# main_board.net
KiCad netlist of a schematic drawn in EAGLE
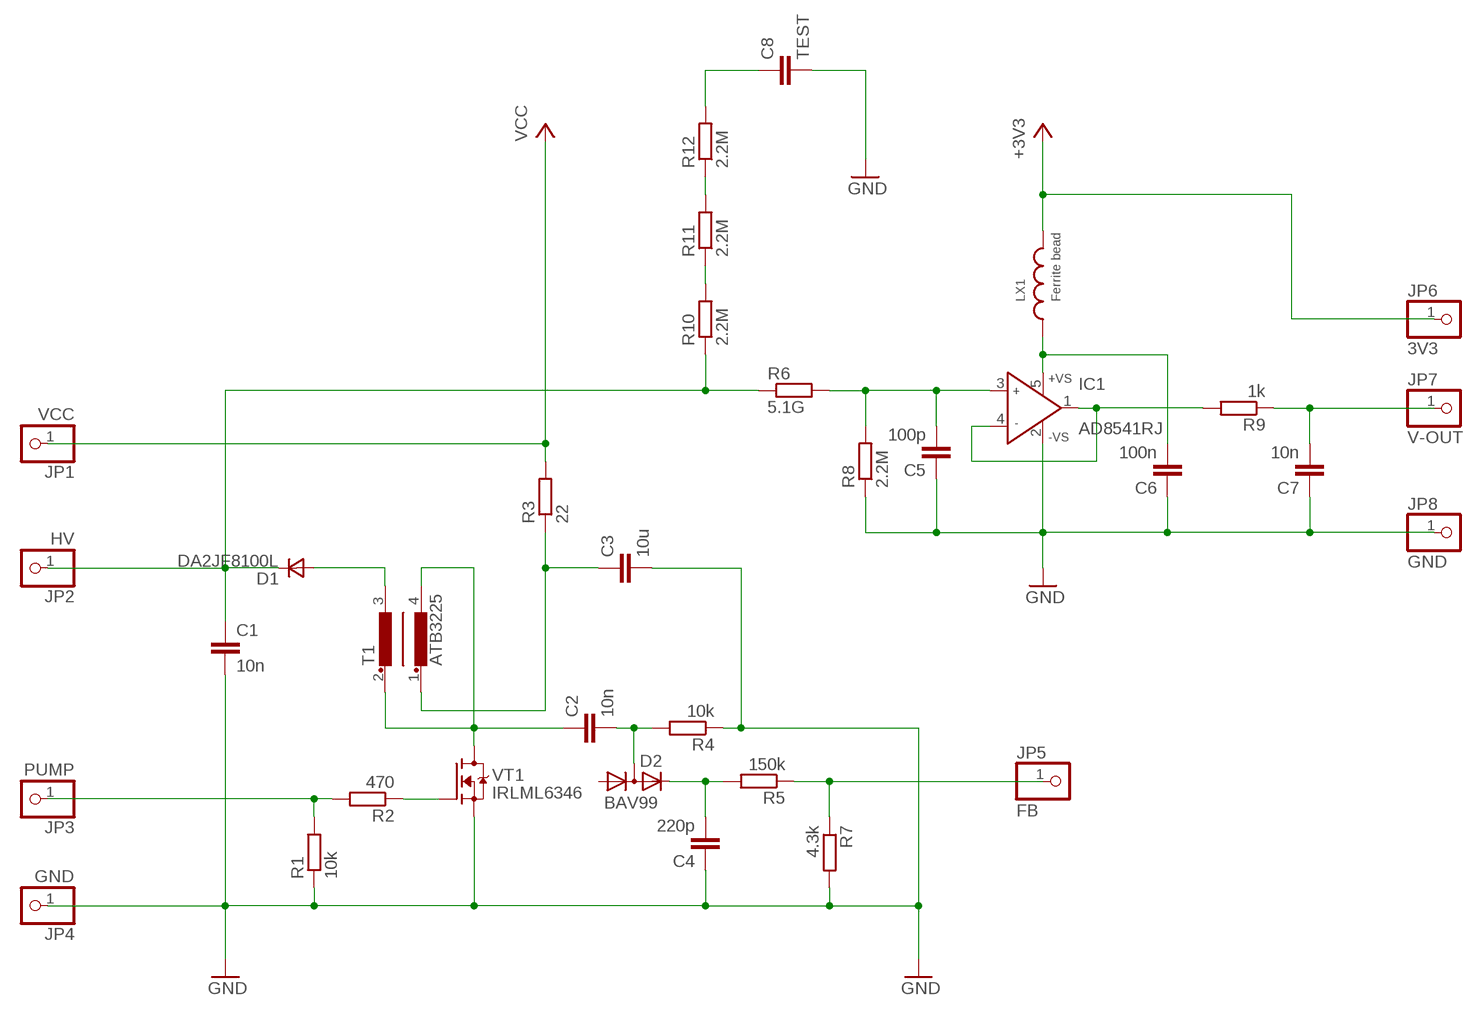
[diagram p0: schematic, sheet 1]

(export (version "E")
  (design (tool "Eeschema 10.0.6"))
  (components
    (comp (ref "C1")
      (value "10n")
      (footprint "eagle-import:C1206")
      (libsource (lib "eagle-import") (part "C-EUC1206"))
    )
    (comp (ref "C2")
      (value "10n")
      (footprint "eagle-import:C0805")
      (libsource (lib "eagle-import") (part "C-EUC0805"))
    )
    (comp (ref "C3")
      (value "10u")
      (footprint "eagle-import:C0805")
      (libsource (lib "eagle-import") (part "C-EUC0805"))
    )
    (comp (ref "C4")
      (value "220p")
      (footprint "eagle-import:C0805")
      (libsource (lib "eagle-import") (part "C-EUC0805"))
    )
    (comp (ref "C5")
      (value "100p")
      (footprint "eagle-import:C0805")
      (libsource (lib "eagle-import") (part "C-EUC0805"))
    )
    (comp (ref "C6")
      (value "100n")
      (footprint "eagle-import:C0805")
      (libsource (lib "eagle-import") (part "C-EUC0805"))
    )
    (comp (ref "C7")
      (value "10n")
      (footprint "eagle-import:C0805")
      (libsource (lib "eagle-import") (part "C-EUC0805"))
    )
    (comp (ref "C8")
      (value "TEST")
      (footprint "eagle-import:C1206")
      (libsource (lib "eagle-import") (part "C-EUC1206"))
    )
    (comp (ref "D1")
      (value "DA2JF8100L")
      (footprint "eagle-import:SOD323")
      (fields (field (name "MPN") "CDSOD323-T05C"))
      (libsource (lib "eagle-import") (part "DSOD323"))
    )
    (comp (ref "D2")
      (value "BAV99")
      (footprint "eagle-import:SOT23")
      (libsource (lib "eagle-import") (part "BAV99"))
    )
    (comp (ref "IC1")
      (value "AD8541RJ")
      (footprint "eagle-import:SOT23-5")
      (fields (field (name "MF") "ALTERA CORPORATION") (field (name "MPN") "AD8541ARTZ-REEL7"))
      (libsource (lib "eagle-import") (part "AD8541RJ"))
    )
    (comp (ref "JP1")
      (value "VCC")
      (footprint "eagle-import:1X01")
      (libsource (lib "eagle-import") (part "PINHD-1X1"))
    )
    (comp (ref "JP2")
      (value "HV")
      (footprint "eagle-import:1X01")
      (libsource (lib "eagle-import") (part "PINHD-1X1"))
    )
    (comp (ref "JP3")
      (value "PUMP")
      (footprint "eagle-import:1X01")
      (libsource (lib "eagle-import") (part "PINHD-1X1"))
    )
    (comp (ref "JP4")
      (value "GND")
      (footprint "eagle-import:1X01")
      (libsource (lib "eagle-import") (part "PINHD-1X1"))
    )
    (comp (ref "JP5")
      (value "FB")
      (footprint "eagle-import:1X01")
      (libsource (lib "eagle-import") (part "PINHD-1X1"))
    )
    (comp (ref "JP6")
      (value "3V3")
      (footprint "eagle-import:1X01")
      (libsource (lib "eagle-import") (part "PINHD-1X1"))
    )
    (comp (ref "JP7")
      (value "V-OUT")
      (footprint "eagle-import:1X01")
      (libsource (lib "eagle-import") (part "PINHD-1X1"))
    )
    (comp (ref "JP8")
      (value "GND")
      (footprint "eagle-import:1X01")
      (libsource (lib "eagle-import") (part "PINHD-1X1"))
    )
    (comp (ref "LX1")
      (value "Ferrite bead")
      (footprint "eagle-import:WE-KI_0805A")
      (libsource (lib "eagle-import") (part "WE-KI_0805A_744760022A"))
    )
    (comp (ref "R1")
      (value "10k")
      (footprint "eagle-import:M0805")
      (libsource (lib "eagle-import") (part "R-EU_M0805"))
    )
    (comp (ref "R2")
      (value "470")
      (footprint "eagle-import:M0805")
      (libsource (lib "eagle-import") (part "R-EU_M0805"))
    )
    (comp (ref "R3")
      (value "22")
      (footprint "eagle-import:M0805")
      (libsource (lib "eagle-import") (part "R-EU_M0805"))
    )
    (comp (ref "R4")
      (value "10k")
      (footprint "eagle-import:M0805")
      (libsource (lib "eagle-import") (part "R-EU_M0805"))
    )
    (comp (ref "R5")
      (value "150k")
      (footprint "eagle-import:M0805")
      (libsource (lib "eagle-import") (part "R-EU_M0805"))
    )
    (comp (ref "R6")
      (value "5.1G")
      (footprint "eagle-import:P0817_22")
      (libsource (lib "eagle-import") (part "R-EU_0817/22"))
    )
    (comp (ref "R7")
      (value "4.3k")
      (footprint "eagle-import:M0805")
      (libsource (lib "eagle-import") (part "R-EU_M0805"))
    )
    (comp (ref "R8")
      (value "2.2M")
      (footprint "eagle-import:M0805")
      (libsource (lib "eagle-import") (part "R-EU_M0805"))
    )
    (comp (ref "R9")
      (value "1k")
      (footprint "eagle-import:M0805")
      (libsource (lib "eagle-import") (part "R-EU_M0805"))
    )
    (comp (ref "R10")
      (value "2.2M")
      (footprint "eagle-import:M0805")
      (libsource (lib "eagle-import") (part "R-EU_M0805"))
    )
    (comp (ref "R11")
      (value "2.2M")
      (footprint "eagle-import:M0805")
      (libsource (lib "eagle-import") (part "R-EU_M0805"))
    )
    (comp (ref "R12")
      (value "2.2M")
      (footprint "eagle-import:M0805")
      (libsource (lib "eagle-import") (part "R-EU_M0805"))
    )
    (comp (ref "T1")
      (value "ATB3225")
      (footprint "eagle-import:ATB3225")
      (libsource (lib "eagle-import") (part "ATB3225"))
    )
    (comp (ref "VT1")
      (value "IRLML6346")
      (footprint "eagle-import:SOT23")
      (libsource (lib "eagle-import") (part "MOSFET-N-SOT23"))
    )
  )
  (nets
    (net (code "1") (name "+3V3") (class "Default")
      (node (ref "JP6") (pin "1") (pinfunction "1_1") (pintype "passive"))
      (node (ref "LX1") (pin "2") (pinfunction "2_2") (pintype "passive"))
    )
    (net (code "2") (name "GND") (class "Default")
      (node (ref "C1") (pin "2") (pinfunction "2_2") (pintype "passive"))
      (node (ref "C3") (pin "2") (pinfunction "2_2") (pintype "passive"))
      (node (ref "C4") (pin "1") (pinfunction "1_1") (pintype "passive"))
      (node (ref "C5") (pin "1") (pinfunction "1_1") (pintype "passive"))
      (node (ref "C6") (pin "1") (pinfunction "1_1") (pintype "passive"))
      (node (ref "C7") (pin "1") (pinfunction "1_1") (pintype "passive"))
      (node (ref "C8") (pin "2") (pinfunction "2_2") (pintype "passive"))
      (node (ref "IC1") (pin "2") (pinfunction "-VS_2") (pintype "input"))
      (node (ref "JP4") (pin "1") (pinfunction "1_1") (pintype "passive"))
      (node (ref "JP8") (pin "1") (pinfunction "1_1") (pintype "passive"))
      (node (ref "R1") (pin "1") (pinfunction "1_1") (pintype "passive"))
      (node (ref "R4") (pin "1") (pinfunction "1_1") (pintype "passive"))
      (node (ref "R7") (pin "2") (pinfunction "2_2") (pintype "passive"))
      (node (ref "R8") (pin "1") (pinfunction "1_1") (pintype "passive"))
      (node (ref "VT1") (pin "2") (pinfunction "S_2") (pintype "passive"))
    )
    (net (code "3") (name "Net-(C3-Pad1)") (class "Default")
      (node (ref "C3") (pin "1") (pinfunction "1_1") (pintype "passive"))
      (node (ref "R3") (pin "1") (pinfunction "1_1") (pintype "passive"))
      (node (ref "T1") (pin "1") (pinfunction "1_1") (pintype "passive"))
    )
    (net (code "4") (name "Net-(C7-Pad2)") (class "Default")
      (node (ref "C7") (pin "2") (pinfunction "2_2") (pintype "passive"))
      (node (ref "JP7") (pin "1") (pinfunction "1_1") (pintype "passive"))
      (node (ref "R9") (pin "1") (pinfunction "1_1") (pintype "passive"))
    )
    (net (code "5") (name "Net-(C8-Pad1)") (class "Default")
      (node (ref "C8") (pin "1") (pinfunction "1_1") (pintype "passive"))
      (node (ref "R12") (pin "2") (pinfunction "2_2") (pintype "passive"))
    )
    (net (code "6") (name "Net-(D1-A)") (class "Default")
      (node (ref "D1") (pin "2") (pinfunction "A_2") (pintype "passive"))
      (node (ref "T1") (pin "3") (pinfunction "3_3") (pintype "passive"))
    )
    (net (code "7") (name "Net-(D1-C)") (class "Default")
      (node (ref "C1") (pin "1") (pinfunction "1_1") (pintype "passive"))
      (node (ref "D1") (pin "1") (pinfunction "C_1") (pintype "passive"))
      (node (ref "JP2") (pin "1") (pinfunction "1_1") (pintype "passive"))
      (node (ref "R10") (pin "1") (pinfunction "1_1") (pintype "passive"))
      (node (ref "R6") (pin "1") (pinfunction "1_1") (pintype "passive"))
    )
    (net (code "8") (name "Net-(D2-K1A2)") (class "Default")
      (node (ref "C2") (pin "2") (pinfunction "2_2") (pintype "passive"))
      (node (ref "D2") (pin "3") (pinfunction "K1A2_3") (pintype "passive"))
      (node (ref "R4") (pin "2") (pinfunction "2_2") (pintype "passive"))
    )
    (net (code "9") (name "Net-(D2-K2)") (class "Default")
      (node (ref "C4") (pin "2") (pinfunction "2_2") (pintype "passive"))
      (node (ref "D2") (pin "2") (pinfunction "K2_2") (pintype "passive"))
      (node (ref "R5") (pin "2") (pinfunction "2_2") (pintype "passive"))
    )
    (net (code "10") (name "Net-(IC1-+VS)") (class "Default")
      (node (ref "C6") (pin "2") (pinfunction "2_2") (pintype "passive"))
      (node (ref "IC1") (pin "5") (pinfunction "+VS_5") (pintype "input"))
      (node (ref "LX1") (pin "1") (pinfunction "1_1") (pintype "passive"))
    )
    (net (code "11") (name "Net-(IC1-IN+)") (class "Default")
      (node (ref "C5") (pin "2") (pinfunction "2_2") (pintype "passive"))
      (node (ref "IC1") (pin "3") (pinfunction "IN+_3") (pintype "input"))
      (node (ref "R6") (pin "2") (pinfunction "2_2") (pintype "passive"))
      (node (ref "R8") (pin "2") (pinfunction "2_2") (pintype "passive"))
    )
    (net (code "12") (name "Net-(IC1-IN-)") (class "Default")
      (node (ref "IC1") (pin "1") (pinfunction "OUT_1") (pintype "output"))
      (node (ref "IC1") (pin "4") (pinfunction "IN-_4") (pintype "input"))
      (node (ref "R9") (pin "2") (pinfunction "2_2") (pintype "passive"))
    )
    (net (code "13") (name "Net-(JP3-Pad1)") (class "Default")
      (node (ref "JP3") (pin "1") (pinfunction "1_1") (pintype "passive"))
      (node (ref "R1") (pin "2") (pinfunction "2_2") (pintype "passive"))
      (node (ref "R2") (pin "2") (pinfunction "2_2") (pintype "passive"))
    )
    (net (code "14") (name "Net-(JP5-Pad1)") (class "Default")
      (node (ref "JP5") (pin "1") (pinfunction "1_1") (pintype "passive"))
      (node (ref "R5") (pin "1") (pinfunction "1_1") (pintype "passive"))
      (node (ref "R7") (pin "1") (pinfunction "1_1") (pintype "passive"))
    )
    (net (code "15") (name "Net-(R10-Pad2)") (class "Default")
      (node (ref "R10") (pin "2") (pinfunction "2_2") (pintype "passive"))
      (node (ref "R11") (pin "1") (pinfunction "1_1") (pintype "passive"))
    )
    (net (code "16") (name "Net-(R11-Pad2)") (class "Default")
      (node (ref "R11") (pin "2") (pinfunction "2_2") (pintype "passive"))
      (node (ref "R12") (pin "1") (pinfunction "1_1") (pintype "passive"))
    )
    (net (code "17") (name "Net-(VT1-D)") (class "Default")
      (node (ref "C2") (pin "1") (pinfunction "1_1") (pintype "passive"))
      (node (ref "T1") (pin "2") (pinfunction "2_2") (pintype "passive"))
      (node (ref "T1") (pin "4") (pinfunction "4_4") (pintype "passive"))
      (node (ref "VT1") (pin "3") (pinfunction "D_3") (pintype "passive"))
    )
    (net (code "18") (name "Net-(VT1-G)") (class "Default")
      (node (ref "R2") (pin "1") (pinfunction "1_1") (pintype "passive"))
      (node (ref "VT1") (pin "1") (pinfunction "G_1") (pintype "passive"))
    )
    (net (code "19") (name "VCC") (class "Default")
      (node (ref "JP1") (pin "1") (pinfunction "1_1") (pintype "passive"))
      (node (ref "R3") (pin "2") (pinfunction "2_2") (pintype "passive"))
    )
    (net (code "20") (name "unconnected-(D2-A1-Pad1)") (class "Default")
      (node (ref "D2") (pin "1") (pinfunction "A1_1") (pintype "passive"))
    )
  )
)
